# S11830_1_2.net
KiCad netlist of a schematic drawn in Altium Designer
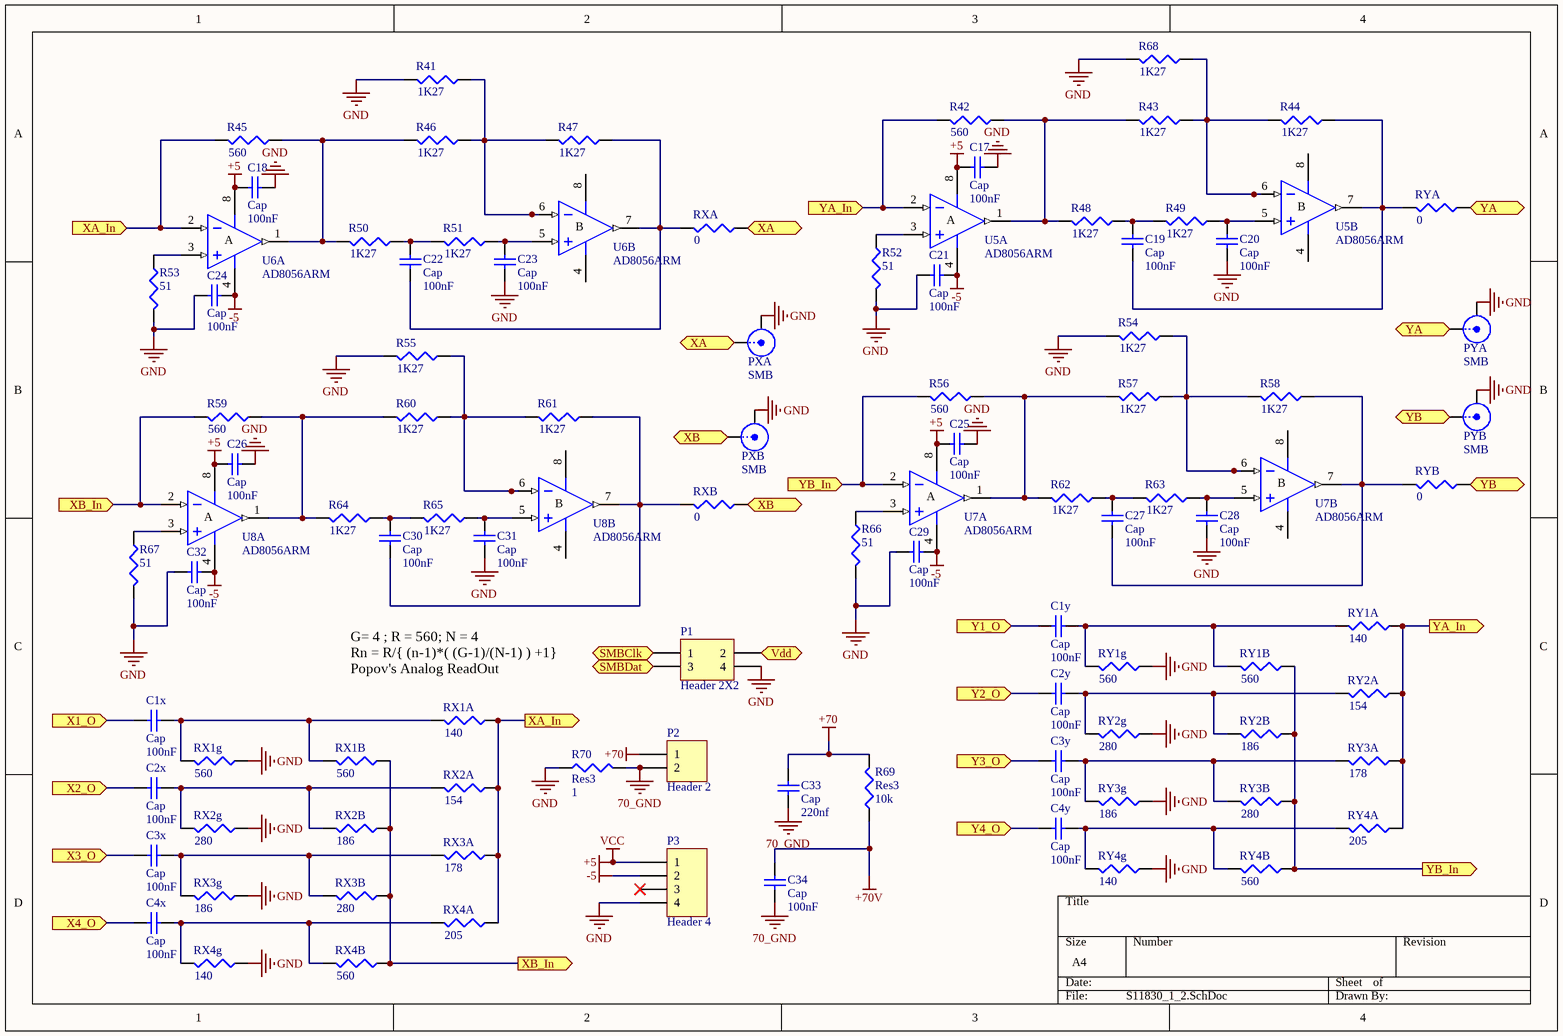
[diagram p0: S11830_1_2.SchDoc]

(export (version "E")
  (design (tool "Eeschema 10.0.6"))
  (components
    (comp (ref "C1x")
      (value "Cap")
      (footprint "1608[0603]")
      (description "Capacitor")
      (fields (field (name "ALTIUM_VALUE") "100nF") (field (name "PUBLISHER") "Altium Limited"))
      (libsource (lib "Miscellaneous Devices") (part "Cap"))
    )
    (comp (ref "C1y")
      (value "Cap")
      (footprint "1608[0603]")
      (description "Capacitor")
      (fields (field (name "ALTIUM_VALUE") "100nF") (field (name "PUBLISHER") "Altium Limited"))
      (libsource (lib "Miscellaneous Devices") (part "Cap"))
    )
    (comp (ref "C2x")
      (value "Cap")
      (footprint "1608[0603]")
      (description "Capacitor")
      (fields (field (name "ALTIUM_VALUE") "100nF") (field (name "PUBLISHER") "Altium Limited"))
      (libsource (lib "Miscellaneous Devices") (part "Cap"))
    )
    (comp (ref "C2y")
      (value "Cap")
      (footprint "1608[0603]")
      (description "Capacitor")
      (fields (field (name "ALTIUM_VALUE") "100nF") (field (name "PUBLISHER") "Altium Limited"))
      (libsource (lib "Miscellaneous Devices") (part "Cap"))
    )
    (comp (ref "C3x")
      (value "Cap")
      (footprint "1608[0603]")
      (description "Capacitor")
      (fields (field (name "ALTIUM_VALUE") "100nF") (field (name "PUBLISHER") "Altium Limited"))
      (libsource (lib "Miscellaneous Devices") (part "Cap"))
    )
    (comp (ref "C3y")
      (value "Cap")
      (footprint "1608[0603]")
      (description "Capacitor")
      (fields (field (name "ALTIUM_VALUE") "100nF") (field (name "PUBLISHER") "Altium Limited"))
      (libsource (lib "Miscellaneous Devices") (part "Cap"))
    )
    (comp (ref "C4x")
      (value "Cap")
      (footprint "1608[0603]")
      (description "Capacitor")
      (fields (field (name "ALTIUM_VALUE") "100nF") (field (name "PUBLISHER") "Altium Limited"))
      (libsource (lib "Miscellaneous Devices") (part "Cap"))
    )
    (comp (ref "C4y")
      (value "Cap")
      (footprint "1608[0603]")
      (description "Capacitor")
      (fields (field (name "ALTIUM_VALUE") "100nF") (field (name "PUBLISHER") "Altium Limited"))
      (libsource (lib "Miscellaneous Devices") (part "Cap"))
    )
    (comp (ref "C17")
      (value "Cap")
      (footprint "1608[0603]")
      (description "Capacitor")
      (fields (field (name "ALTIUM_VALUE") "100nF") (field (name "PUBLISHER") "Altium Limited"))
      (libsource (lib "Miscellaneous Devices") (part "Cap"))
    )
    (comp (ref "C18")
      (value "Cap")
      (footprint "1608[0603]")
      (description "Capacitor")
      (fields (field (name "ALTIUM_VALUE") "100nF") (field (name "PUBLISHER") "Altium Limited"))
      (libsource (lib "Miscellaneous Devices") (part "Cap"))
    )
    (comp (ref "C19")
      (value "Cap")
      (footprint "1608[0603]")
      (description "Capacitor")
      (fields (field (name "ALTIUM_VALUE") "100nF") (field (name "PUBLISHER") "Altium Limited"))
      (libsource (lib "Miscellaneous Devices") (part "Cap"))
    )
    (comp (ref "C20")
      (value "Cap")
      (footprint "1608[0603]")
      (description "Capacitor")
      (fields (field (name "ALTIUM_VALUE") "100nF") (field (name "PUBLISHER") "Altium Limited"))
      (libsource (lib "Miscellaneous Devices") (part "Cap"))
    )
    (comp (ref "C21")
      (value "Cap")
      (footprint "1608[0603]")
      (description "Capacitor")
      (fields (field (name "ALTIUM_VALUE") "100nF") (field (name "PUBLISHER") "Altium Limited"))
      (libsource (lib "Miscellaneous Devices") (part "Cap"))
    )
    (comp (ref "C22")
      (value "Cap")
      (footprint "1608[0603]")
      (description "Capacitor")
      (fields (field (name "ALTIUM_VALUE") "100nF") (field (name "PUBLISHER") "Altium Limited"))
      (libsource (lib "Miscellaneous Devices") (part "Cap"))
    )
    (comp (ref "C23")
      (value "Cap")
      (footprint "1608[0603]")
      (description "Capacitor")
      (fields (field (name "ALTIUM_VALUE") "100nF") (field (name "PUBLISHER") "Altium Limited"))
      (libsource (lib "Miscellaneous Devices") (part "Cap"))
    )
    (comp (ref "C24")
      (value "Cap")
      (footprint "1608[0603]")
      (description "Capacitor")
      (fields (field (name "ALTIUM_VALUE") "100nF") (field (name "PUBLISHER") "Altium Limited"))
      (libsource (lib "Miscellaneous Devices") (part "Cap"))
    )
    (comp (ref "C25")
      (value "Cap")
      (footprint "1608[0603]")
      (description "Capacitor")
      (fields (field (name "ALTIUM_VALUE") "100nF") (field (name "PUBLISHER") "Altium Limited"))
      (libsource (lib "Miscellaneous Devices") (part "Cap"))
    )
    (comp (ref "C26")
      (value "Cap")
      (footprint "1608[0603]")
      (description "Capacitor")
      (fields (field (name "ALTIUM_VALUE") "100nF") (field (name "PUBLISHER") "Altium Limited"))
      (libsource (lib "Miscellaneous Devices") (part "Cap"))
    )
    (comp (ref "C27")
      (value "Cap")
      (footprint "1608[0603]")
      (description "Capacitor")
      (fields (field (name "ALTIUM_VALUE") "100nF") (field (name "PUBLISHER") "Altium Limited"))
      (libsource (lib "Miscellaneous Devices") (part "Cap"))
    )
    (comp (ref "C28")
      (value "Cap")
      (footprint "1608[0603]")
      (description "Capacitor")
      (fields (field (name "ALTIUM_VALUE") "100nF") (field (name "PUBLISHER") "Altium Limited"))
      (libsource (lib "Miscellaneous Devices") (part "Cap"))
    )
    (comp (ref "C29")
      (value "Cap")
      (footprint "1608[0603]")
      (description "Capacitor")
      (fields (field (name "ALTIUM_VALUE") "100nF") (field (name "PUBLISHER") "Altium Limited"))
      (libsource (lib "Miscellaneous Devices") (part "Cap"))
    )
    (comp (ref "C30")
      (value "Cap")
      (footprint "1608[0603]")
      (description "Capacitor")
      (fields (field (name "ALTIUM_VALUE") "100nF") (field (name "PUBLISHER") "Altium Limited"))
      (libsource (lib "Miscellaneous Devices") (part "Cap"))
    )
    (comp (ref "C31")
      (value "Cap")
      (footprint "1608[0603]")
      (description "Capacitor")
      (fields (field (name "ALTIUM_VALUE") "100nF") (field (name "PUBLISHER") "Altium Limited"))
      (libsource (lib "Miscellaneous Devices") (part "Cap"))
    )
    (comp (ref "C32")
      (value "Cap")
      (footprint "1608[0603]")
      (description "Capacitor")
      (fields (field (name "ALTIUM_VALUE") "100nF") (field (name "PUBLISHER") "Altium Limited"))
      (libsource (lib "Miscellaneous Devices") (part "Cap"))
    )
    (comp (ref "C33")
      (value "Cap")
      (footprint "6-0805_N")
      (description "Capacitor")
      (fields (field (name "ALTIUM_VALUE") "220nf") (field (name "PUBLISHER") "Altium Limited"))
      (libsource (lib "Miscellaneous Devices") (part "Cap"))
    )
    (comp (ref "C34")
      (value "Cap")
      (footprint "6-0805_N")
      (description "Capacitor")
      (fields (field (name "ALTIUM_VALUE") "100nF") (field (name "PUBLISHER") "Altium Limited"))
      (libsource (lib "Miscellaneous Devices") (part "Cap"))
    )
    (comp (ref "P1")
      (value "Header 2X2")
      (footprint "HDR2X2")
      (description "Header, 2-Pin, Dual row")
      (fields (field (name "PUBLISHER") "Altium Limited"))
      (libsource (lib "Miscellaneous Connectors") (part "Header 2X2"))
    )
    (comp (ref "P2")
      (value "Header 2")
      (footprint "HDR1X2")
      (description "Header, 2-Pin")
      (fields (field (name "PUBLISHER") "Altium Limited"))
      (libsource (lib "Miscellaneous Connectors") (part "Header 2"))
    )
    (comp (ref "P3")
      (value "Header 4")
      (footprint "HDR1X4")
      (description "Header, 4-Pin")
      (fields (field (name "PUBLISHER") "Altium Limited"))
      (libsource (lib "Miscellaneous Connectors") (part "Header 4"))
    )
    (comp (ref "PXA")
      (value "SMB")
      (footprint "SMB_V-RJ45")
      (description "SMB Straight Connector")
      (fields (field (name "PUBLISHER") "Altium Limited"))
      (libsource (lib "Miscellaneous Connectors") (part "SMB"))
    )
    (comp (ref "PXB")
      (value "SMB")
      (footprint "SMB_V-RJ45")
      (description "SMB Straight Connector")
      (fields (field (name "PUBLISHER") "Altium Limited"))
      (libsource (lib "Miscellaneous Connectors") (part "SMB"))
    )
    (comp (ref "PYA")
      (value "SMB")
      (footprint "SMB_V-RJ45")
      (description "SMB Straight Connector")
      (fields (field (name "PUBLISHER") "Altium Limited"))
      (libsource (lib "Miscellaneous Connectors") (part "SMB"))
    )
    (comp (ref "PYB")
      (value "SMB")
      (footprint "SMB_V-RJ45")
      (description "SMB Straight Connector")
      (fields (field (name "PUBLISHER") "Altium Limited"))
      (libsource (lib "Miscellaneous Connectors") (part "SMB"))
    )
    (comp (ref "R41")
      (value "1K27")
      (footprint "J1-0603")
      (description "Resistor")
      (fields (field (name "Comment") "Res3") (field (name "PUBLISHER") "Altium Limited"))
      (libsource (lib "Miscellaneous Devices") (part "Res3"))
    )
    (comp (ref "R42")
      (value "560")
      (footprint "J1-0603")
      (description "Resistor")
      (fields (field (name "Comment") "Res3") (field (name "PUBLISHER") "Altium Limited"))
      (libsource (lib "Miscellaneous Devices") (part "Res3"))
    )
    (comp (ref "R43")
      (value "1K27")
      (footprint "J1-0603")
      (description "Resistor")
      (fields (field (name "Comment") "Res3") (field (name "PUBLISHER") "Altium Limited"))
      (libsource (lib "Miscellaneous Devices") (part "Res3"))
    )
    (comp (ref "R44")
      (value "1K27")
      (footprint "J1-0603")
      (description "Resistor")
      (fields (field (name "Comment") "Res3") (field (name "PUBLISHER") "Altium Limited"))
      (libsource (lib "Miscellaneous Devices") (part "Res3"))
    )
    (comp (ref "R45")
      (value "560")
      (footprint "J1-0603")
      (description "Resistor")
      (fields (field (name "Comment") "Res3") (field (name "PUBLISHER") "Altium Limited"))
      (libsource (lib "Miscellaneous Devices") (part "Res3"))
    )
    (comp (ref "R46")
      (value "1K27")
      (footprint "J1-0603")
      (description "Resistor")
      (fields (field (name "Comment") "Res3") (field (name "PUBLISHER") "Altium Limited"))
      (libsource (lib "Miscellaneous Devices") (part "Res3"))
    )
    (comp (ref "R47")
      (value "1K27")
      (footprint "J1-0603")
      (description "Resistor")
      (fields (field (name "Comment") "Res3") (field (name "PUBLISHER") "Altium Limited"))
      (libsource (lib "Miscellaneous Devices") (part "Res3"))
    )
    (comp (ref "R48")
      (value "1K27")
      (footprint "J1-0603")
      (description "Resistor")
      (fields (field (name "Comment") "Res3") (field (name "PUBLISHER") "Altium Limited"))
      (libsource (lib "Miscellaneous Devices") (part "Res3"))
    )
    (comp (ref "R49")
      (value "1K27")
      (footprint "J1-0603")
      (description "Resistor")
      (fields (field (name "Comment") "Res3") (field (name "PUBLISHER") "Altium Limited"))
      (libsource (lib "Miscellaneous Devices") (part "Res3"))
    )
    (comp (ref "R50")
      (value "1K27")
      (footprint "J1-0603")
      (description "Resistor")
      (fields (field (name "Comment") "Res3") (field (name "PUBLISHER") "Altium Limited"))
      (libsource (lib "Miscellaneous Devices") (part "Res3"))
    )
    (comp (ref "R51")
      (value "1K27")
      (footprint "J1-0603")
      (description "Resistor")
      (fields (field (name "Comment") "Res3") (field (name "PUBLISHER") "Altium Limited"))
      (libsource (lib "Miscellaneous Devices") (part "Res3"))
    )
    (comp (ref "R52")
      (value "51")
      (footprint "J1-0603")
      (description "Resistor")
      (fields (field (name "Comment") "Res3") (field (name "PUBLISHER") "Altium Limited"))
      (libsource (lib "Miscellaneous Devices") (part "Res3"))
    )
    (comp (ref "R53")
      (value "51")
      (footprint "J1-0603")
      (description "Resistor")
      (fields (field (name "Comment") "Res3") (field (name "PUBLISHER") "Altium Limited"))
      (libsource (lib "Miscellaneous Devices") (part "Res3"))
    )
    (comp (ref "R54")
      (value "1K27")
      (footprint "J1-0603")
      (description "Resistor")
      (fields (field (name "Comment") "Res3") (field (name "PUBLISHER") "Altium Limited"))
      (libsource (lib "Miscellaneous Devices") (part "Res3"))
    )
    (comp (ref "R55")
      (value "1K27")
      (footprint "J1-0603")
      (description "Resistor")
      (fields (field (name "Comment") "Res3") (field (name "PUBLISHER") "Altium Limited"))
      (libsource (lib "Miscellaneous Devices") (part "Res3"))
    )
    (comp (ref "R56")
      (value "560")
      (footprint "J1-0603")
      (description "Resistor")
      (fields (field (name "Comment") "Res3") (field (name "PUBLISHER") "Altium Limited"))
      (libsource (lib "Miscellaneous Devices") (part "Res3"))
    )
    (comp (ref "R57")
      (value "1K27")
      (footprint "J1-0603")
      (description "Resistor")
      (fields (field (name "Comment") "Res3") (field (name "PUBLISHER") "Altium Limited"))
      (libsource (lib "Miscellaneous Devices") (part "Res3"))
    )
    (comp (ref "R58")
      (value "1K27")
      (footprint "J1-0603")
      (description "Resistor")
      (fields (field (name "Comment") "Res3") (field (name "PUBLISHER") "Altium Limited"))
      (libsource (lib "Miscellaneous Devices") (part "Res3"))
    )
    (comp (ref "R59")
      (value "560")
      (footprint "J1-0603")
      (description "Resistor")
      (fields (field (name "Comment") "Res3") (field (name "PUBLISHER") "Altium Limited"))
      (libsource (lib "Miscellaneous Devices") (part "Res3"))
    )
    (comp (ref "R60")
      (value "1K27")
      (footprint "J1-0603")
      (description "Resistor")
      (fields (field (name "Comment") "Res3") (field (name "PUBLISHER") "Altium Limited"))
      (libsource (lib "Miscellaneous Devices") (part "Res3"))
    )
    (comp (ref "R61")
      (value "1K27")
      (footprint "J1-0603")
      (description "Resistor")
      (fields (field (name "Comment") "Res3") (field (name "PUBLISHER") "Altium Limited"))
      (libsource (lib "Miscellaneous Devices") (part "Res3"))
    )
    (comp (ref "R62")
      (value "1K27")
      (footprint "J1-0603")
      (description "Resistor")
      (fields (field (name "Comment") "Res3") (field (name "PUBLISHER") "Altium Limited"))
      (libsource (lib "Miscellaneous Devices") (part "Res3"))
    )
    (comp (ref "R63")
      (value "1K27")
      (footprint "J1-0603")
      (description "Resistor")
      (fields (field (name "Comment") "Res3") (field (name "PUBLISHER") "Altium Limited"))
      (libsource (lib "Miscellaneous Devices") (part "Res3"))
    )
    (comp (ref "R64")
      (value "1K27")
      (footprint "J1-0603")
      (description "Resistor")
      (fields (field (name "Comment") "Res3") (field (name "PUBLISHER") "Altium Limited"))
      (libsource (lib "Miscellaneous Devices") (part "Res3"))
    )
    (comp (ref "R65")
      (value "1K27")
      (footprint "J1-0603")
      (description "Resistor")
      (fields (field (name "Comment") "Res3") (field (name "PUBLISHER") "Altium Limited"))
      (libsource (lib "Miscellaneous Devices") (part "Res3"))
    )
    (comp (ref "R66")
      (value "51")
      (footprint "J1-0603")
      (description "Resistor")
      (fields (field (name "Comment") "Res3") (field (name "PUBLISHER") "Altium Limited"))
      (libsource (lib "Miscellaneous Devices") (part "Res3"))
    )
    (comp (ref "R67")
      (value "51")
      (footprint "J1-0603")
      (description "Resistor")
      (fields (field (name "Comment") "Res3") (field (name "PUBLISHER") "Altium Limited"))
      (libsource (lib "Miscellaneous Devices") (part "Res3"))
    )
    (comp (ref "R68")
      (value "1K27")
      (footprint "J1-0603")
      (description "Resistor")
      (fields (field (name "Comment") "Res3") (field (name "PUBLISHER") "Altium Limited"))
      (libsource (lib "Miscellaneous Devices") (part "Res3"))
    )
    (comp (ref "R69")
      (value "Res3")
      (footprint "6-0805_N")
      (description "Resistor")
      (fields (field (name "ALTIUM_VALUE") "10k") (field (name "PUBLISHER") "Altium Limited"))
      (libsource (lib "Miscellaneous Devices") (part "Res3"))
    )
    (comp (ref "R70")
      (value "Res3")
      (footprint "6-0805_N")
      (description "Resistor")
      (fields (field (name "ALTIUM_VALUE") "1") (field (name "PUBLISHER") "Altium Limited"))
      (libsource (lib "Miscellaneous Devices") (part "Res3"))
    )
    (comp (ref "RX1A")
      (value "140")
      (footprint "J1-0603")
      (description "Resistor")
      (fields (field (name "Comment") "Res3") (field (name "PUBLISHER") "Altium Limited"))
      (libsource (lib "Miscellaneous Devices") (part "Res3"))
    )
    (comp (ref "RX1B")
      (value "560")
      (footprint "J1-0603")
      (description "Resistor")
      (fields (field (name "Comment") "Res3") (field (name "PUBLISHER") "Altium Limited"))
      (libsource (lib "Miscellaneous Devices") (part "Res3"))
    )
    (comp (ref "RX1g")
      (value "560")
      (footprint "J1-0603")
      (description "Resistor")
      (fields (field (name "Comment") "Res3") (field (name "PUBLISHER") "Altium Limited"))
      (libsource (lib "Miscellaneous Devices") (part "Res3"))
    )
    (comp (ref "RX2A")
      (value "154")
      (footprint "J1-0603")
      (description "Resistor")
      (fields (field (name "Comment") "Res3") (field (name "PUBLISHER") "Altium Limited"))
      (libsource (lib "Miscellaneous Devices") (part "Res3"))
    )
    (comp (ref "RX2B")
      (value "186")
      (footprint "J1-0603")
      (description "Resistor")
      (fields (field (name "Comment") "Res3") (field (name "PUBLISHER") "Altium Limited"))
      (libsource (lib "Miscellaneous Devices") (part "Res3"))
    )
    (comp (ref "RX2g")
      (value "280")
      (footprint "J1-0603")
      (description "Resistor")
      (fields (field (name "Comment") "Res3") (field (name "PUBLISHER") "Altium Limited"))
      (libsource (lib "Miscellaneous Devices") (part "Res3"))
    )
    (comp (ref "RX3A")
      (value "178")
      (footprint "J1-0603")
      (description "Resistor")
      (fields (field (name "Comment") "Res3") (field (name "PUBLISHER") "Altium Limited"))
      (libsource (lib "Miscellaneous Devices") (part "Res3"))
    )
    (comp (ref "RX3B")
      (value "280")
      (footprint "J1-0603")
      (description "Resistor")
      (fields (field (name "Comment") "Res3") (field (name "PUBLISHER") "Altium Limited"))
      (libsource (lib "Miscellaneous Devices") (part "Res3"))
    )
    (comp (ref "RX3g")
      (value "186")
      (footprint "J1-0603")
      (description "Resistor")
      (fields (field (name "Comment") "Res3") (field (name "PUBLISHER") "Altium Limited"))
      (libsource (lib "Miscellaneous Devices") (part "Res3"))
    )
    (comp (ref "RX4A")
      (value "205")
      (footprint "J1-0603")
      (description "Resistor")
      (fields (field (name "Comment") "Res3") (field (name "PUBLISHER") "Altium Limited"))
      (libsource (lib "Miscellaneous Devices") (part "Res3"))
    )
    (comp (ref "RX4B")
      (value "560")
      (footprint "J1-0603")
      (description "Resistor")
      (fields (field (name "Comment") "Res3") (field (name "PUBLISHER") "Altium Limited"))
      (libsource (lib "Miscellaneous Devices") (part "Res3"))
    )
    (comp (ref "RX4g")
      (value "140")
      (footprint "J1-0603")
      (description "Resistor")
      (fields (field (name "Comment") "Res3") (field (name "PUBLISHER") "Altium Limited"))
      (libsource (lib "Miscellaneous Devices") (part "Res3"))
    )
    (comp (ref "RXA")
      (value "0")
      (footprint "J1-0603")
      (description "Resistor")
      (fields (field (name "Comment") "Res3") (field (name "PUBLISHER") "Altium Limited"))
      (libsource (lib "Miscellaneous Devices") (part "Res3"))
    )
    (comp (ref "RXB")
      (value "0")
      (footprint "J1-0603")
      (description "Resistor")
      (fields (field (name "Comment") "Res3") (field (name "PUBLISHER") "Altium Limited"))
      (libsource (lib "Miscellaneous Devices") (part "Res3"))
    )
    (comp (ref "RY1A")
      (value "140")
      (footprint "J1-0603")
      (description "Resistor")
      (fields (field (name "Comment") "Res3") (field (name "PUBLISHER") "Altium Limited"))
      (libsource (lib "Miscellaneous Devices") (part "Res3"))
    )
    (comp (ref "RY1B")
      (value "560")
      (footprint "J1-0603")
      (description "Resistor")
      (fields (field (name "Comment") "Res3") (field (name "PUBLISHER") "Altium Limited"))
      (libsource (lib "Miscellaneous Devices") (part "Res3"))
    )
    (comp (ref "RY1g")
      (value "560")
      (footprint "J1-0603")
      (description "Resistor")
      (fields (field (name "Comment") "Res3") (field (name "PUBLISHER") "Altium Limited"))
      (libsource (lib "Miscellaneous Devices") (part "Res3"))
    )
    (comp (ref "RY2A")
      (value "154")
      (footprint "J1-0603")
      (description "Resistor")
      (fields (field (name "Comment") "Res3") (field (name "PUBLISHER") "Altium Limited"))
      (libsource (lib "Miscellaneous Devices") (part "Res3"))
    )
    (comp (ref "RY2B")
      (value "186")
      (footprint "J1-0603")
      (description "Resistor")
      (fields (field (name "Comment") "Res3") (field (name "PUBLISHER") "Altium Limited"))
      (libsource (lib "Miscellaneous Devices") (part "Res3"))
    )
    (comp (ref "RY2g")
      (value "280")
      (footprint "J1-0603")
      (description "Resistor")
      (fields (field (name "Comment") "Res3") (field (name "PUBLISHER") "Altium Limited"))
      (libsource (lib "Miscellaneous Devices") (part "Res3"))
    )
    (comp (ref "RY3A")
      (value "178")
      (footprint "J1-0603")
      (description "Resistor")
      (fields (field (name "Comment") "Res3") (field (name "PUBLISHER") "Altium Limited"))
      (libsource (lib "Miscellaneous Devices") (part "Res3"))
    )
    (comp (ref "RY3B")
      (value "280")
      (footprint "J1-0603")
      (description "Resistor")
      (fields (field (name "Comment") "Res3") (field (name "PUBLISHER") "Altium Limited"))
      (libsource (lib "Miscellaneous Devices") (part "Res3"))
    )
    (comp (ref "RY3g")
      (value "186")
      (footprint "J1-0603")
      (description "Resistor")
      (fields (field (name "Comment") "Res3") (field (name "PUBLISHER") "Altium Limited"))
      (libsource (lib "Miscellaneous Devices") (part "Res3"))
    )
    (comp (ref "RY4A")
      (value "205")
      (footprint "J1-0603")
      (description "Resistor")
      (fields (field (name "Comment") "Res3") (field (name "PUBLISHER") "Altium Limited"))
      (libsource (lib "Miscellaneous Devices") (part "Res3"))
    )
    (comp (ref "RY4B")
      (value "560")
      (footprint "J1-0603")
      (description "Resistor")
      (fields (field (name "Comment") "Res3") (field (name "PUBLISHER") "Altium Limited"))
      (libsource (lib "Miscellaneous Devices") (part "Res3"))
    )
    (comp (ref "RY4g")
      (value "140")
      (footprint "J1-0603")
      (description "Resistor")
      (fields (field (name "Comment") "Res3") (field (name "PUBLISHER") "Altium Limited"))
      (libsource (lib "Miscellaneous Devices") (part "Res3"))
    )
    (comp (ref "RYA")
      (value "0")
      (footprint "J1-0603")
      (description "Resistor")
      (fields (field (name "Comment") "Res3") (field (name "PUBLISHER") "Altium Limited"))
      (libsource (lib "Miscellaneous Devices") (part "Res3"))
    )
    (comp (ref "RYB")
      (value "0")
      (footprint "J1-0603")
      (description "Resistor")
      (fields (field (name "Comment") "Res3") (field (name "PUBLISHER") "Altium Limited"))
      (libsource (lib "Miscellaneous Devices") (part "Res3"))
    )
    (comp (ref "U5")
      (value "AD8056ARM")
      (footprint "SO8_M")
      (description "Low Cost, 300MHz Voltage Feedback Amplifier")
      (fields (field (name "PUBLISHER") "Altium Limited"))
      (libsource (lib "AD Operational Amplifier") (part "AD8056ARM"))
    )
    (comp (ref "U6")
      (value "AD8056ARM")
      (footprint "SO8_M")
      (description "Low Cost, 300MHz Voltage Feedback Amplifier")
      (fields (field (name "PUBLISHER") "Altium Limited"))
      (libsource (lib "AD Operational Amplifier") (part "AD8056ARM"))
    )
    (comp (ref "U7")
      (value "AD8056ARM")
      (footprint "SO8_M")
      (description "Low Cost, 300MHz Voltage Feedback Amplifier")
      (fields (field (name "PUBLISHER") "Altium Limited"))
      (libsource (lib "AD Operational Amplifier") (part "AD8056ARM"))
    )
    (comp (ref "U8")
      (value "AD8056ARM")
      (footprint "SO8_M")
      (description "Low Cost, 300MHz Voltage Feedback Amplifier")
      (fields (field (name "PUBLISHER") "Altium Limited"))
      (libsource (lib "AD Operational Amplifier") (part "AD8056ARM"))
    )
  )
  (nets
    (net (code "1") (name "+5") (class "Default")
      (node (ref "C17") (pin "1") (pinfunction "1_1") (pintype "passive"))
      (node (ref "C18") (pin "1") (pinfunction "1_1") (pintype "passive"))
      (node (ref "C25") (pin "1") (pinfunction "1_1") (pintype "passive"))
      (node (ref "C26") (pin "1") (pinfunction "1_1") (pintype "passive"))
      (node (ref "P3") (pin "1") (pinfunction "1_1") (pintype "passive"))
      (node (ref "U5") (pin "8") (pinfunction "V+_8") (pintype "power_in"))
      (node (ref "U6") (pin "8") (pinfunction "V+_8") (pintype "power_in"))
      (node (ref "U7") (pin "8") (pinfunction "V+_8") (pintype "power_in"))
      (node (ref "U8") (pin "8") (pinfunction "V+_8") (pintype "power_in"))
    )
    (net (code "2") (name "+70") (class "Default")
      (node (ref "C33") (pin "2") (pinfunction "2_2") (pintype "passive"))
      (node (ref "P2") (pin "1") (pinfunction "1_1") (pintype "passive"))
      (node (ref "R69") (pin "2") (pinfunction "2_2") (pintype "passive"))
    )
    (net (code "3") (name "+70V") (class "Default")
      (node (ref "C34") (pin "2") (pinfunction "2_2") (pintype "passive"))
      (node (ref "R69") (pin "1") (pinfunction "1_1") (pintype "passive"))
    )
    (net (code "4") (name "-5") (class "Default")
      (node (ref "C21") (pin "2") (pinfunction "2_2") (pintype "passive"))
      (node (ref "C24") (pin "2") (pinfunction "2_2") (pintype "passive"))
      (node (ref "C29") (pin "2") (pinfunction "2_2") (pintype "passive"))
      (node (ref "C32") (pin "2") (pinfunction "2_2") (pintype "passive"))
      (node (ref "P3") (pin "2") (pinfunction "2_2") (pintype "passive"))
      (node (ref "U5") (pin "4") (pinfunction "V-_4") (pintype "power_in"))
      (node (ref "U6") (pin "4") (pinfunction "V-_4") (pintype "power_in"))
      (node (ref "U7") (pin "4") (pinfunction "V-_4") (pintype "power_in"))
      (node (ref "U8") (pin "4") (pinfunction "V-_4") (pintype "power_in"))
    )
    (net (code "5") (name "/SMBClk") (class "Default")
      (node (ref "P1") (pin "1") (pinfunction "1_1") (pintype "passive"))
    )
    (net (code "6") (name "/SMBDat") (class "Default")
      (node (ref "P1") (pin "3") (pinfunction "3_3") (pintype "passive"))
    )
    (net (code "7") (name "/Vdd") (class "Default")
      (node (ref "P1") (pin "2") (pinfunction "2_2") (pintype "passive"))
    )
    (net (code "8") (name "/X1_O") (class "Default")
      (node (ref "C1x") (pin "1") (pinfunction "1_1") (pintype "passive"))
    )
    (net (code "9") (name "/X2_O") (class "Default")
      (node (ref "C2x") (pin "1") (pinfunction "1_1") (pintype "passive"))
    )
    (net (code "10") (name "/X3_O") (class "Default")
      (node (ref "C3x") (pin "1") (pinfunction "1_1") (pintype "passive"))
    )
    (net (code "11") (name "/X4_O") (class "Default")
      (node (ref "C4x") (pin "1") (pinfunction "1_1") (pintype "passive"))
    )
    (net (code "12") (name "/XA") (class "Default")
      (node (ref "PXA") (pin "1") (pinfunction "X_1") (pintype "passive"))
      (node (ref "RXA") (pin "1") (pinfunction "1_1") (pintype "passive"))
    )
    (net (code "13") (name "/XA_In") (class "Default")
      (node (ref "R45") (pin "2") (pinfunction "2_2") (pintype "passive"))
      (node (ref "RX1A") (pin "1") (pinfunction "1_1") (pintype "passive"))
      (node (ref "RX2A") (pin "1") (pinfunction "1_1") (pintype "passive"))
      (node (ref "RX3A") (pin "1") (pinfunction "1_1") (pintype "passive"))
      (node (ref "RX4A") (pin "1") (pinfunction "1_1") (pintype "passive"))
      (node (ref "U6") (pin "2") (pinfunction "IN-_2") (pintype "input"))
    )
    (net (code "14") (name "/XB") (class "Default")
      (node (ref "PXB") (pin "1") (pinfunction "X_1") (pintype "passive"))
      (node (ref "RXB") (pin "1") (pinfunction "1_1") (pintype "passive"))
    )
    (net (code "15") (name "/XB_In") (class "Default")
      (node (ref "R59") (pin "2") (pinfunction "2_2") (pintype "passive"))
      (node (ref "RX1B") (pin "1") (pinfunction "1_1") (pintype "passive"))
      (node (ref "RX2B") (pin "1") (pinfunction "1_1") (pintype "passive"))
      (node (ref "RX3B") (pin "1") (pinfunction "1_1") (pintype "passive"))
      (node (ref "RX4B") (pin "1") (pinfunction "1_1") (pintype "passive"))
      (node (ref "U8") (pin "2") (pinfunction "IN-_2") (pintype "input"))
    )
    (net (code "16") (name "/Y1_O") (class "Default")
      (node (ref "C1y") (pin "1") (pinfunction "1_1") (pintype "passive"))
    )
    (net (code "17") (name "/Y2_O") (class "Default")
      (node (ref "C2y") (pin "1") (pinfunction "1_1") (pintype "passive"))
    )
    (net (code "18") (name "/Y3_O") (class "Default")
      (node (ref "C3y") (pin "1") (pinfunction "1_1") (pintype "passive"))
    )
    (net (code "19") (name "/Y4_O") (class "Default")
      (node (ref "C4y") (pin "1") (pinfunction "1_1") (pintype "passive"))
    )
    (net (code "20") (name "/YA") (class "Default")
      (node (ref "PYA") (pin "1") (pinfunction "X_1") (pintype "passive"))
      (node (ref "RYA") (pin "1") (pinfunction "1_1") (pintype "passive"))
    )
    (net (code "21") (name "/YA_In") (class "Default")
      (node (ref "R42") (pin "2") (pinfunction "2_2") (pintype "passive"))
      (node (ref "RY1A") (pin "1") (pinfunction "1_1") (pintype "passive"))
      (node (ref "RY2A") (pin "1") (pinfunction "1_1") (pintype "passive"))
      (node (ref "RY3A") (pin "1") (pinfunction "1_1") (pintype "passive"))
      (node (ref "RY4A") (pin "1") (pinfunction "1_1") (pintype "passive"))
      (node (ref "U5") (pin "2") (pinfunction "IN-_2") (pintype "input"))
    )
    (net (code "22") (name "/YB") (class "Default")
      (node (ref "PYB") (pin "1") (pinfunction "X_1") (pintype "passive"))
      (node (ref "RYB") (pin "1") (pinfunction "1_1") (pintype "passive"))
    )
    (net (code "23") (name "/YB_In") (class "Default")
      (node (ref "R56") (pin "2") (pinfunction "2_2") (pintype "passive"))
      (node (ref "RY1B") (pin "1") (pinfunction "1_1") (pintype "passive"))
      (node (ref "RY2B") (pin "1") (pinfunction "1_1") (pintype "passive"))
      (node (ref "RY3B") (pin "1") (pinfunction "1_1") (pintype "passive"))
      (node (ref "RY4B") (pin "1") (pinfunction "1_1") (pintype "passive"))
      (node (ref "U7") (pin "2") (pinfunction "IN-_2") (pintype "input"))
    )
    (net (code "24") (name "70_GND") (class "Default")
      (node (ref "C33") (pin "1") (pinfunction "1_1") (pintype "passive"))
      (node (ref "C34") (pin "1") (pinfunction "1_1") (pintype "passive"))
      (node (ref "P2") (pin "2") (pinfunction "2_2") (pintype "passive"))
      (node (ref "R70") (pin "2") (pinfunction "2_2") (pintype "passive"))
    )
    (net (code "25") (name "GND") (class "Default")
      (node (ref "C17") (pin "2") (pinfunction "2_2") (pintype "passive"))
      (node (ref "C18") (pin "2") (pinfunction "2_2") (pintype "passive"))
      (node (ref "C20") (pin "2") (pinfunction "2_2") (pintype "passive"))
      (node (ref "C21") (pin "1") (pinfunction "1_1") (pintype "passive"))
      (node (ref "C23") (pin "2") (pinfunction "2_2") (pintype "passive"))
      (node (ref "C24") (pin "1") (pinfunction "1_1") (pintype "passive"))
      (node (ref "C25") (pin "2") (pinfunction "2_2") (pintype "passive"))
      (node (ref "C26") (pin "2") (pinfunction "2_2") (pintype "passive"))
      (node (ref "C28") (pin "2") (pinfunction "2_2") (pintype "passive"))
      (node (ref "C29") (pin "1") (pinfunction "1_1") (pintype "passive"))
      (node (ref "C31") (pin "2") (pinfunction "2_2") (pintype "passive"))
      (node (ref "C32") (pin "1") (pinfunction "1_1") (pintype "passive"))
      (node (ref "P1") (pin "4") (pinfunction "4_4") (pintype "passive"))
      (node (ref "P3") (pin "4") (pinfunction "4_4") (pintype "passive"))
      (node (ref "PXA") (pin "2") (pinfunction "Y_2") (pintype "passive"))
      (node (ref "PXB") (pin "2") (pinfunction "Y_2") (pintype "passive"))
      (node (ref "PYA") (pin "2") (pinfunction "Y_2") (pintype "passive"))
      (node (ref "PYB") (pin "2") (pinfunction "Y_2") (pintype "passive"))
      (node (ref "R41") (pin "2") (pinfunction "2_2") (pintype "passive"))
      (node (ref "R52") (pin "2") (pinfunction "2_2") (pintype "passive"))
      (node (ref "R53") (pin "2") (pinfunction "2_2") (pintype "passive"))
      (node (ref "R54") (pin "2") (pinfunction "2_2") (pintype "passive"))
      (node (ref "R55") (pin "2") (pinfunction "2_2") (pintype "passive"))
      (node (ref "R66") (pin "2") (pinfunction "2_2") (pintype "passive"))
      (node (ref "R67") (pin "2") (pinfunction "2_2") (pintype "passive"))
      (node (ref "R68") (pin "2") (pinfunction "2_2") (pintype "passive"))
      (node (ref "R70") (pin "1") (pinfunction "1_1") (pintype "passive"))
      (node (ref "RX1g") (pin "1") (pinfunction "1_1") (pintype "passive"))
      (node (ref "RX2g") (pin "1") (pinfunction "1_1") (pintype "passive"))
      (node (ref "RX3g") (pin "1") (pinfunction "1_1") (pintype "passive"))
      (node (ref "RX4g") (pin "1") (pinfunction "1_1") (pintype "passive"))
      (node (ref "RY1g") (pin "1") (pinfunction "1_1") (pintype "passive"))
      (node (ref "RY2g") (pin "1") (pinfunction "1_1") (pintype "passive"))
      (node (ref "RY3g") (pin "1") (pinfunction "1_1") (pintype "passive"))
      (node (ref "RY4g") (pin "1") (pinfunction "1_1") (pintype "passive"))
    )
    (net (code "26") (name "Net-(C1x-Pad2)") (class "Default")
      (node (ref "C1x") (pin "2") (pinfunction "2_2") (pintype "passive"))
      (node (ref "RX1A") (pin "2") (pinfunction "2_2") (pintype "passive"))
      (node (ref "RX1B") (pin "2") (pinfunction "2_2") (pintype "passive"))
      (node (ref "RX1g") (pin "2") (pinfunction "2_2") (pintype "passive"))
    )
    (net (code "27") (name "Net-(C1y-Pad2)") (class "Default")
      (node (ref "C1y") (pin "2") (pinfunction "2_2") (pintype "passive"))
      (node (ref "RY1A") (pin "2") (pinfunction "2_2") (pintype "passive"))
      (node (ref "RY1B") (pin "2") (pinfunction "2_2") (pintype "passive"))
      (node (ref "RY1g") (pin "2") (pinfunction "2_2") (pintype "passive"))
    )
    (net (code "28") (name "Net-(C2x-Pad2)") (class "Default")
      (node (ref "C2x") (pin "2") (pinfunction "2_2") (pintype "passive"))
      (node (ref "RX2A") (pin "2") (pinfunction "2_2") (pintype "passive"))
      (node (ref "RX2B") (pin "2") (pinfunction "2_2") (pintype "passive"))
      (node (ref "RX2g") (pin "2") (pinfunction "2_2") (pintype "passive"))
    )
    (net (code "29") (name "Net-(C2y-Pad2)") (class "Default")
      (node (ref "C2y") (pin "2") (pinfunction "2_2") (pintype "passive"))
      (node (ref "RY2A") (pin "2") (pinfunction "2_2") (pintype "passive"))
      (node (ref "RY2B") (pin "2") (pinfunction "2_2") (pintype "passive"))
      (node (ref "RY2g") (pin "2") (pinfunction "2_2") (pintype "passive"))
    )
    (net (code "30") (name "Net-(C3x-Pad2)") (class "Default")
      (node (ref "C3x") (pin "2") (pinfunction "2_2") (pintype "passive"))
      (node (ref "RX3A") (pin "2") (pinfunction "2_2") (pintype "passive"))
      (node (ref "RX3B") (pin "2") (pinfunction "2_2") (pintype "passive"))
      (node (ref "RX3g") (pin "2") (pinfunction "2_2") (pintype "passive"))
    )
    (net (code "31") (name "Net-(C3y-Pad2)") (class "Default")
      (node (ref "C3y") (pin "2") (pinfunction "2_2") (pintype "passive"))
      (node (ref "RY3A") (pin "2") (pinfunction "2_2") (pintype "passive"))
      (node (ref "RY3B") (pin "2") (pinfunction "2_2") (pintype "passive"))
      (node (ref "RY3g") (pin "2") (pinfunction "2_2") (pintype "passive"))
    )
    (net (code "32") (name "Net-(C4x-Pad2)") (class "Default")
      (node (ref "C4x") (pin "2") (pinfunction "2_2") (pintype "passive"))
      (node (ref "RX4A") (pin "2") (pinfunction "2_2") (pintype "passive"))
      (node (ref "RX4B") (pin "2") (pinfunction "2_2") (pintype "passive"))
      (node (ref "RX4g") (pin "2") (pinfunction "2_2") (pintype "passive"))
    )
    (net (code "33") (name "Net-(C4y-Pad2)") (class "Default")
      (node (ref "C4y") (pin "2") (pinfunction "2_2") (pintype "passive"))
      (node (ref "RY4A") (pin "2") (pinfunction "2_2") (pintype "passive"))
      (node (ref "RY4B") (pin "2") (pinfunction "2_2") (pintype "passive"))
      (node (ref "RY4g") (pin "2") (pinfunction "2_2") (pintype "passive"))
    )
    (net (code "34") (name "Net-(C19-Pad1)") (class "Default")
      (node (ref "C19") (pin "1") (pinfunction "1_1") (pintype "passive"))
      (node (ref "R48") (pin "1") (pinfunction "1_1") (pintype "passive"))
      (node (ref "R49") (pin "2") (pinfunction "2_2") (pintype "passive"))
    )
    (net (code "35") (name "Net-(C22-Pad1)") (class "Default")
      (node (ref "C22") (pin "1") (pinfunction "1_1") (pintype "passive"))
      (node (ref "R50") (pin "1") (pinfunction "1_1") (pintype "passive"))
      (node (ref "R51") (pin "2") (pinfunction "2_2") (pintype "passive"))
    )
    (net (code "36") (name "Net-(C27-Pad1)") (class "Default")
      (node (ref "C27") (pin "1") (pinfunction "1_1") (pintype "passive"))
      (node (ref "R62") (pin "1") (pinfunction "1_1") (pintype "passive"))
      (node (ref "R63") (pin "2") (pinfunction "2_2") (pintype "passive"))
    )
    (net (code "37") (name "Net-(C30-Pad1)") (class "Default")
      (node (ref "C30") (pin "1") (pinfunction "1_1") (pintype "passive"))
      (node (ref "R64") (pin "1") (pinfunction "1_1") (pintype "passive"))
      (node (ref "R65") (pin "2") (pinfunction "2_2") (pintype "passive"))
    )
    (net (code "38") (name "Net-(U5A-IN+)") (class "Default")
      (node (ref "R52") (pin "1") (pinfunction "1_1") (pintype "passive"))
      (node (ref "U5") (pin "3") (pinfunction "IN+_3") (pintype "input"))
    )
    (net (code "39") (name "Net-(U5A-OUT)") (class "Default")
      (node (ref "R42") (pin "1") (pinfunction "1_1") (pintype "passive"))
      (node (ref "R43") (pin "2") (pinfunction "2_2") (pintype "passive"))
      (node (ref "R48") (pin "2") (pinfunction "2_2") (pintype "passive"))
      (node (ref "U5") (pin "1") (pinfunction "OUT_1") (pintype "output"))
    )
    (net (code "40") (name "Net-(U5B-IN+)") (class "Default")
      (node (ref "C20") (pin "1") (pinfunction "1_1") (pintype "passive"))
      (node (ref "R49") (pin "1") (pinfunction "1_1") (pintype "passive"))
      (node (ref "U5") (pin "5") (pinfunction "IN+_5") (pintype "input"))
    )
    (net (code "41") (name "Net-(U5B-IN-)") (class "Default")
      (node (ref "R43") (pin "1") (pinfunction "1_1") (pintype "passive"))
      (node (ref "R44") (pin "2") (pinfunction "2_2") (pintype "passive"))
      (node (ref "R68") (pin "1") (pinfunction "1_1") (pintype "passive"))
      (node (ref "U5") (pin "6") (pinfunction "IN-_6") (pintype "input"))
    )
    (net (code "42") (name "Net-(U5B-OUT)") (class "Default")
      (node (ref "C19") (pin "2") (pinfunction "2_2") (pintype "passive"))
      (node (ref "R44") (pin "1") (pinfunction "1_1") (pintype "passive"))
      (node (ref "RYA") (pin "2") (pinfunction "2_2") (pintype "passive"))
      (node (ref "U5") (pin "7") (pinfunction "OUT_7") (pintype "output"))
    )
    (net (code "43") (name "Net-(U6A-IN+)") (class "Default")
      (node (ref "R53") (pin "1") (pinfunction "1_1") (pintype "passive"))
      (node (ref "U6") (pin "3") (pinfunction "IN+_3") (pintype "input"))
    )
    (net (code "44") (name "Net-(U6A-OUT)") (class "Default")
      (node (ref "R45") (pin "1") (pinfunction "1_1") (pintype "passive"))
      (node (ref "R46") (pin "2") (pinfunction "2_2") (pintype "passive"))
      (node (ref "R50") (pin "2") (pinfunction "2_2") (pintype "passive"))
      (node (ref "U6") (pin "1") (pinfunction "OUT_1") (pintype "output"))
    )
    (net (code "45") (name "Net-(U6B-IN+)") (class "Default")
      (node (ref "C23") (pin "1") (pinfunction "1_1") (pintype "passive"))
      (node (ref "R51") (pin "1") (pinfunction "1_1") (pintype "passive"))
      (node (ref "U6") (pin "5") (pinfunction "IN+_5") (pintype "input"))
    )
    (net (code "46") (name "Net-(U6B-IN-)") (class "Default")
      (node (ref "R41") (pin "1") (pinfunction "1_1") (pintype "passive"))
      (node (ref "R46") (pin "1") (pinfunction "1_1") (pintype "passive"))
      (node (ref "R47") (pin "2") (pinfunction "2_2") (pintype "passive"))
      (node (ref "U6") (pin "6") (pinfunction "IN-_6") (pintype "input"))
    )
    (net (code "47") (name "Net-(U6B-OUT)") (class "Default")
      (node (ref "C22") (pin "2") (pinfunction "2_2") (pintype "passive"))
      (node (ref "R47") (pin "1") (pinfunction "1_1") (pintype "passive"))
      (node (ref "RXA") (pin "2") (pinfunction "2_2") (pintype "passive"))
      (node (ref "U6") (pin "7") (pinfunction "OUT_7") (pintype "output"))
    )
    (net (code "48") (name "Net-(U7A-IN+)") (class "Default")
      (node (ref "R66") (pin "1") (pinfunction "1_1") (pintype "passive"))
      (node (ref "U7") (pin "3") (pinfunction "IN+_3") (pintype "input"))
    )
    (net (code "49") (name "Net-(U7A-OUT)") (class "Default")
      (node (ref "R56") (pin "1") (pinfunction "1_1") (pintype "passive"))
      (node (ref "R57") (pin "2") (pinfunction "2_2") (pintype "passive"))
      (node (ref "R62") (pin "2") (pinfunction "2_2") (pintype "passive"))
      (node (ref "U7") (pin "1") (pinfunction "OUT_1") (pintype "output"))
    )
    (net (code "50") (name "Net-(U7B-IN+)") (class "Default")
      (node (ref "C28") (pin "1") (pinfunction "1_1") (pintype "passive"))
      (node (ref "R63") (pin "1") (pinfunction "1_1") (pintype "passive"))
      (node (ref "U7") (pin "5") (pinfunction "IN+_5") (pintype "input"))
    )
    (net (code "51") (name "Net-(U7B-IN-)") (class "Default")
      (node (ref "R54") (pin "1") (pinfunction "1_1") (pintype "passive"))
      (node (ref "R57") (pin "1") (pinfunction "1_1") (pintype "passive"))
      (node (ref "R58") (pin "2") (pinfunction "2_2") (pintype "passive"))
      (node (ref "U7") (pin "6") (pinfunction "IN-_6") (pintype "input"))
    )
    (net (code "52") (name "Net-(U7B-OUT)") (class "Default")
      (node (ref "C27") (pin "2") (pinfunction "2_2") (pintype "passive"))
      (node (ref "R58") (pin "1") (pinfunction "1_1") (pintype "passive"))
      (node (ref "RYB") (pin "2") (pinfunction "2_2") (pintype "passive"))
      (node (ref "U7") (pin "7") (pinfunction "OUT_7") (pintype "output"))
    )
    (net (code "53") (name "Net-(U8A-IN+)") (class "Default")
      (node (ref "R67") (pin "1") (pinfunction "1_1") (pintype "passive"))
      (node (ref "U8") (pin "3") (pinfunction "IN+_3") (pintype "input"))
    )
    (net (code "54") (name "Net-(U8A-OUT)") (class "Default")
      (node (ref "R59") (pin "1") (pinfunction "1_1") (pintype "passive"))
      (node (ref "R60") (pin "2") (pinfunction "2_2") (pintype "passive"))
      (node (ref "R64") (pin "2") (pinfunction "2_2") (pintype "passive"))
      (node (ref "U8") (pin "1") (pinfunction "OUT_1") (pintype "output"))
    )
    (net (code "55") (name "Net-(U8B-IN+)") (class "Default")
      (node (ref "C31") (pin "1") (pinfunction "1_1") (pintype "passive"))
      (node (ref "R65") (pin "1") (pinfunction "1_1") (pintype "passive"))
      (node (ref "U8") (pin "5") (pinfunction "IN+_5") (pintype "input"))
    )
    (net (code "56") (name "Net-(U8B-IN-)") (class "Default")
      (node (ref "R55") (pin "1") (pinfunction "1_1") (pintype "passive"))
      (node (ref "R60") (pin "1") (pinfunction "1_1") (pintype "passive"))
      (node (ref "R61") (pin "2") (pinfunction "2_2") (pintype "passive"))
      (node (ref "U8") (pin "6") (pinfunction "IN-_6") (pintype "input"))
    )
    (net (code "57") (name "Net-(U8B-OUT)") (class "Default")
      (node (ref "C30") (pin "2") (pinfunction "2_2") (pintype "passive"))
      (node (ref "R61") (pin "1") (pinfunction "1_1") (pintype "passive"))
      (node (ref "RXB") (pin "2") (pinfunction "2_2") (pintype "passive"))
      (node (ref "U8") (pin "7") (pinfunction "OUT_7") (pintype "output"))
    )
    (net (code "58") (name "unconnected-(P3-Pad3)") (class "Default")
      (node (ref "P3") (pin "3") (pinfunction "3_3") (pintype "passive+no_connect"))
    )
    (net (code "59") (name "unconnected-(U5B-V+-Pad8)") (class "Default")
      (node (ref "U5") (pin "8") (pinfunction "V+_8") (pintype "power_in"))
    )
    (net (code "60") (name "unconnected-(U5B-V--Pad4)") (class "Default")
      (node (ref "U5") (pin "4") (pinfunction "V-_4") (pintype "power_in"))
    )
    (net (code "61") (name "unconnected-(U6B-V+-Pad8)") (class "Default")
      (node (ref "U6") (pin "8") (pinfunction "V+_8") (pintype "power_in"))
    )
    (net (code "62") (name "unconnected-(U6B-V--Pad4)") (class "Default")
      (node (ref "U6") (pin "4") (pinfunction "V-_4") (pintype "power_in"))
    )
    (net (code "63") (name "unconnected-(U7B-V+-Pad8)") (class "Default")
      (node (ref "U7") (pin "8") (pinfunction "V+_8") (pintype "power_in"))
    )
    (net (code "64") (name "unconnected-(U7B-V--Pad4)") (class "Default")
      (node (ref "U7") (pin "4") (pinfunction "V-_4") (pintype "power_in"))
    )
    (net (code "65") (name "unconnected-(U8B-V+-Pad8)") (class "Default")
      (node (ref "U8") (pin "8") (pinfunction "V+_8") (pintype "power_in"))
    )
    (net (code "66") (name "unconnected-(U8B-V--Pad4)") (class "Default")
      (node (ref "U8") (pin "4") (pinfunction "V-_4") (pintype "power_in"))
    )
  )
)
